# Cyusb3314_Indicator.net
KiCad netlist of a schematic drawn in Altium Designer
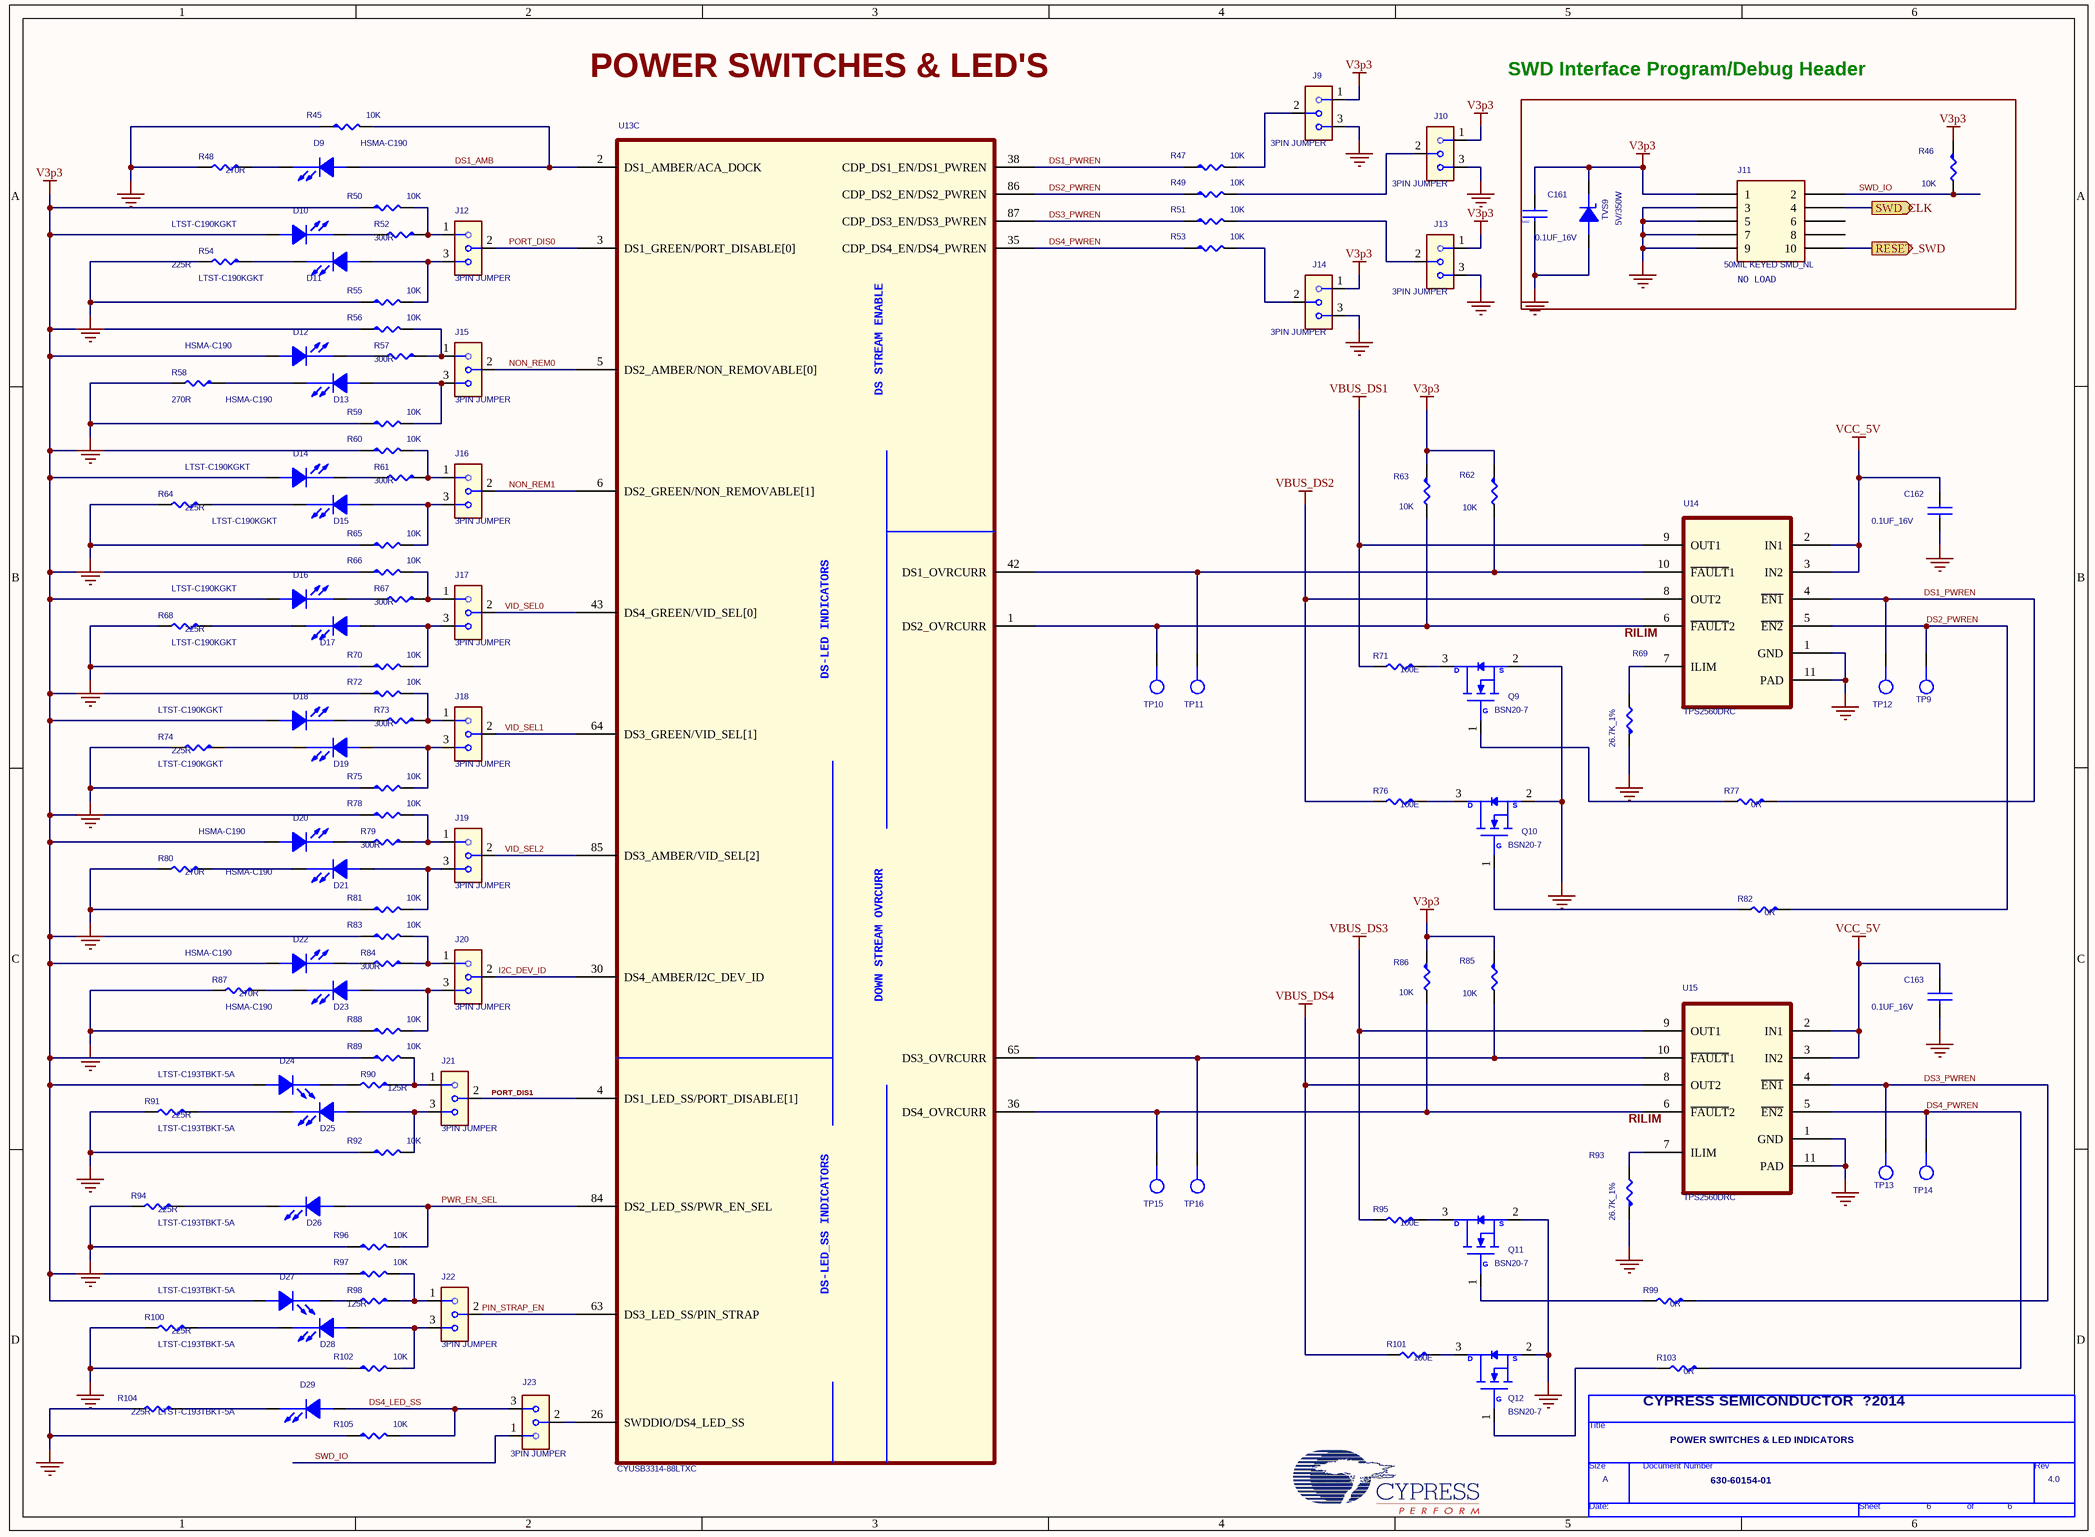
[diagram p0: Cyusb3314_Indicator.SchDoc]

(export (version "E")
  (design (tool "Eeschema 10.0.6"))
  (components
    (comp (ref "C161")
      (value "0.1UF_16V")
      (footprint "CAPC1005X55M")
      (description "CAP .1UF 16V CERAMIC Y5V 0402")
      (fields
        (field (name "CY_PART#") "730R-10010")
        (field (name "MANUFACTURER") "Panasonic - ECG")
        (field (name "CREATED BY") "SNF")
      )
      (libsource (lib "*") (part "0.1 uFd 0402"))
    )
    (comp (ref "C162")
      (value "0.1UF_16V")
      (footprint "CAPC1005X56M")
      (libsource (lib "*") (part "CAPACITOR NON-POL"))
    )
    (comp (ref "C163")
      (value "0.1UF_16V")
      (footprint "CAPC1005X56M")
      (libsource (lib "*") (part "CAPACITOR NON-POL"))
    )
    (comp (ref "D9") (value "HSMA-C190") (libsource (lib "*") (part "LED")))
    (comp (ref "D10") (value "LTST-C190KGKT") (libsource (lib "*") (part "LED")))
    (comp (ref "D11") (value "LTST-C190KGKT") (libsource (lib "*") (part "LED")))
    (comp (ref "D12") (value "HSMA-C190") (libsource (lib "*") (part "LED")))
    (comp (ref "D13") (value "HSMA-C190") (libsource (lib "*") (part "LED")))
    (comp (ref "D14") (value "LTST-C190KGKT") (libsource (lib "*") (part "LED")))
    (comp (ref "D15") (value "LTST-C190KGKT") (libsource (lib "*") (part "LED")))
    (comp (ref "D16") (value "LTST-C190KGKT") (libsource (lib "*") (part "LED")))
    (comp (ref "D17") (value "LTST-C190KGKT") (libsource (lib "*") (part "LED")))
    (comp (ref "D18") (value "LTST-C190KGKT") (libsource (lib "*") (part "LED")))
    (comp (ref "D19") (value "LTST-C190KGKT") (libsource (lib "*") (part "LED")))
    (comp (ref "D20") (value "HSMA-C190") (libsource (lib "*") (part "LED")))
    (comp (ref "D21") (value "HSMA-C190") (libsource (lib "*") (part "LED")))
    (comp (ref "D22") (value "HSMA-C190") (libsource (lib "*") (part "LED")))
    (comp (ref "D23") (value "HSMA-C190") (libsource (lib "*") (part "LED")))
    (comp (ref "D24") (value "LTST-C193TBKT-5A") (libsource (lib "*") (part "LED")))
    (comp (ref "D25") (value "LTST-C193TBKT-5A") (libsource (lib "*") (part "LED")))
    (comp (ref "D26") (value "LTST-C193TBKT-5A") (libsource (lib "*") (part "LED")))
    (comp (ref "D27") (value "LTST-C193TBKT-5A") (libsource (lib "*") (part "LED")))
    (comp (ref "D28") (value "LTST-C193TBKT-5A") (libsource (lib "*") (part "LED")))
    (comp (ref "D29") (value "LTST-C193TBKT-5A") (libsource (lib "*") (part "LED")))
    (comp (ref "J9")
      (value "3PIN JUMPER")
      (description "CONN HEADER VERT 3POS .100 TIN")
      (fields (field (name "PART NUMBER") "3-644456-3") (field (name "MANUFACTURER") "Tyco Electronics"))
      (libsource (lib "") (part "3PIN JUM_1"))
    )
    (comp (ref "J10")
      (value "3PIN JUMPER")
      (description "CONN HEADER VERT 3POS .100 TIN")
      (fields (field (name "MANUFACTURER") "Tyco Electronics") (field (name "PART NUMBER") "3-644456-3"))
      (libsource (lib "") (part "3PIN JUM_1"))
    )
    (comp (ref "J11")
      (value "50MIL KEYED SMD_NL")
      (footprint "SAMTEC_FTSH-105-01-L-DV-K")
      (description "CONN HEADER 10 PIN 50MIL KEYED SMD")
      (fields
        (field (name "PART NUMBER") "FTSH-105-01-L-DV-K")
        (field (name "MANUFACTURER") "Samtec")
        (field (name "LAST EDIT BY") "SNF")
      )
      (libsource (lib "*") (part "10 Pin Header 50mil Keyed SMD"))
    )
    (comp (ref "J12")
      (value "3PIN JUMPER")
      (description "CONN HEADER VERT 3POS .100 TIN")
      (fields (field (name "PART NUMBER") "3-644456-3") (field (name "MANUFACTURER") "Tyco Electronics"))
      (libsource (lib "*") (part "3PIN JUM"))
    )
    (comp (ref "J13")
      (value "3PIN JUMPER")
      (description "CONN HEADER VERT 3POS .100 TIN")
      (fields (field (name "PART NUMBER") "3-644456-3") (field (name "MANUFACTURER") "Tyco Electronics"))
      (libsource (lib "") (part "3PIN JUM_1"))
    )
    (comp (ref "J14")
      (value "3PIN JUMPER")
      (description "CONN HEADER VERT 3POS .100 TIN")
      (fields (field (name "MANUFACTURER") "Tyco Electronics") (field (name "PART NUMBER") "3-644456-3"))
      (libsource (lib "") (part "3PIN JUM_1"))
    )
    (comp (ref "J15")
      (value "3PIN JUMPER")
      (description "CONN HEADER VERT 3POS .100 TIN")
      (fields (field (name "PART NUMBER") "3-644456-3") (field (name "MANUFACTURER") "Tyco Electronics"))
      (libsource (lib "*") (part "3PIN JUM"))
    )
    (comp (ref "J16")
      (value "3PIN JUMPER")
      (description "CONN HEADER VERT 3POS .100 TIN")
      (fields (field (name "PART NUMBER") "3-644456-3") (field (name "MANUFACTURER") "Tyco Electronics"))
      (libsource (lib "*") (part "3PIN JUM"))
    )
    (comp (ref "J17")
      (value "3PIN JUMPER")
      (description "CONN HEADER VERT 3POS .100 TIN")
      (fields (field (name "MANUFACTURER") "Tyco Electronics") (field (name "PART NUMBER") "3-644456-3"))
      (libsource (lib "*") (part "3PIN JUM"))
    )
    (comp (ref "J18")
      (value "3PIN JUMPER")
      (description "CONN HEADER VERT 3POS .100 TIN")
      (fields (field (name "PART NUMBER") "3-644456-3") (field (name "MANUFACTURER") "Tyco Electronics"))
      (libsource (lib "*") (part "3PIN JUM"))
    )
    (comp (ref "J19")
      (value "3PIN JUMPER")
      (description "CONN HEADER VERT 3POS .100 TIN")
      (fields (field (name "MANUFACTURER") "Tyco Electronics") (field (name "PART NUMBER") "3-644456-3"))
      (libsource (lib "*") (part "3PIN JUM"))
    )
    (comp (ref "J20")
      (value "3PIN JUMPER")
      (description "CONN HEADER VERT 3POS .100 TIN")
      (fields (field (name "MANUFACTURER") "Tyco Electronics") (field (name "PART NUMBER") "3-644456-3"))
      (libsource (lib "*") (part "3PIN JUM"))
    )
    (comp (ref "J21")
      (value "3PIN JUMPER")
      (description "CONN HEADER VERT 3POS .100 TIN")
      (fields (field (name "PART NUMBER") "3-644456-3") (field (name "MANUFACTURER") "Tyco Electronics"))
      (libsource (lib "*") (part "3PIN JUM"))
    )
    (comp (ref "J22")
      (value "3PIN JUMPER")
      (description "CONN HEADER VERT 3POS .100 TIN")
      (fields (field (name "PART NUMBER") "3-644456-3") (field (name "MANUFACTURER") "Tyco Electronics"))
      (libsource (lib "*") (part "3PIN JUM"))
    )
    (comp (ref "J23")
      (value "3PIN JUMPER")
      (description "CONN HEADER VERT 3POS .100 TIN")
      (fields (field (name "PART NUMBER") "3-644456-3") (field (name "MANUFACTURER") "Tyco Electronics"))
      (libsource (lib "") (part "3PIN JUM_2"))
    )
    (comp (ref "Q9")
      (value "BSN20-7")
      (description "MOSFET N-CH 50V 500MA SOT23")
      (fields (field (name "MANUFACTURER") "Diodes Inc"))
      (libsource (lib "*") (part "BSN20-7"))
    )
    (comp (ref "Q10")
      (value "BSN20-7")
      (description "MOSFET N-CH 50V 500MA SOT23")
      (fields (field (name "MANUFACTURER") "Diodes Inc"))
      (libsource (lib "*") (part "BSN20-7"))
    )
    (comp (ref "Q11")
      (value "BSN20-7")
      (description "MOSFET N-CH 50V 500MA SOT23")
      (fields (field (name "MANUFACTURER") "Diodes Inc"))
      (libsource (lib "*") (part "BSN20-7"))
    )
    (comp (ref "Q12")
      (value "BSN20-7")
      (description "MOSFET N-CH 50V 500MA SOT23")
      (fields (field (name "MANUFACTURER") "Diodes Inc"))
      (libsource (lib "*") (part "BSN20-7"))
    )
    (comp (ref "R45")
      (value "10K")
      (footprint "RESC1005X40M")
      (description "RES 10.0K OHM 1/10W 1% 0603 SMD")
      (fields (field (name "MANUFACTURER") "Panasonic - ECG") (field (name "PART NUMBER") "ERJ-3EKF1002V"))
      (libsource (lib "*") (part "R_Dup1"))
    )
    (comp (ref "R46")
      (value "10K")
      (footprint "RESC1005X40M")
      (description "RES 10.0K OHM 1/10W 1% 0603 SMD")
      (fields (field (name "MANUFACTURER") "Panasonic - ECG") (field (name "PART NUMBER") "ERJ-3EKF1002V"))
      (libsource (lib "*") (part "R_Dup1"))
    )
    (comp (ref "R47")
      (value "10K")
      (footprint "RESC1005X40M")
      (description "RES 10.0K OHM 1/10W 1% 0603 SMD")
      (fields (field (name "MANUFACTURER") "Panasonic - ECG") (field (name "PART NUMBER") "ERJ-3EKF1002V"))
      (libsource (lib "*") (part "R_Dup1"))
    )
    (comp (ref "R48") (value "270R") (footprint "RESC1608X50M") (libsource (lib "*") (part "R_Dup1")))
    (comp (ref "R49")
      (value "10K")
      (footprint "RESC1005X40M")
      (description "RES 10.0K OHM 1/10W 1% 0603 SMD")
      (fields (field (name "MANUFACTURER") "Panasonic - ECG") (field (name "PART NUMBER") "ERJ-3EKF1002V"))
      (libsource (lib "*") (part "R_Dup1"))
    )
    (comp (ref "R50")
      (value "10K")
      (footprint "RESC1005X40M")
      (description "RES 10.0K OHM 1/10W 1% 0603 SMD")
      (fields (field (name "MANUFACTURER") "Panasonic - ECG") (field (name "PART NUMBER") "ERJ-3EKF1002V"))
      (libsource (lib "*") (part "R_Dup1"))
    )
    (comp (ref "R51")
      (value "10K")
      (footprint "RESC1005X40M")
      (description "RES 10.0K OHM 1/10W 1% 0603 SMD")
      (fields (field (name "MANUFACTURER") "Panasonic - ECG") (field (name "PART NUMBER") "ERJ-3EKF1002V"))
      (libsource (lib "*") (part "R_Dup1"))
    )
    (comp (ref "R52") (value "300R") (footprint "RESC2012X65M") (libsource (lib "*") (part "R_Dup1")))
    (comp (ref "R53")
      (value "10K")
      (footprint "RESC1005X40M")
      (description "RES 10.0K OHM 1/10W 1% 0603 SMD")
      (fields (field (name "MANUFACTURER") "Panasonic - ECG") (field (name "PART NUMBER") "ERJ-3EKF1002V"))
      (libsource (lib "*") (part "R_Dup1"))
    )
    (comp (ref "R54") (value "225R") (footprint "RESC1608X50M") (libsource (lib "*") (part "R_Dup1")))
    (comp (ref "R55")
      (value "10K")
      (footprint "RESC1005X40M")
      (description "RES 10.0K OHM 1/10W 1% 0603 SMD")
      (fields (field (name "MANUFACTURER") "Panasonic - ECG") (field (name "PART NUMBER") "ERJ-3EKF1002V"))
      (libsource (lib "*") (part "R_Dup1"))
    )
    (comp (ref "R56")
      (value "10K")
      (footprint "RESC1005X40M")
      (description "RES 10.0K OHM 1/10W 1% 0603 SMD")
      (fields (field (name "PART NUMBER") "ERJ-3EKF1002V") (field (name "MANUFACTURER") "Panasonic - ECG"))
      (libsource (lib "*") (part "R_Dup1"))
    )
    (comp (ref "R57") (value "300R") (footprint "RESC2012X65M") (libsource (lib "*") (part "R_Dup1")))
    (comp (ref "R58") (value "270R") (footprint "RESC1608X50M") (libsource (lib "*") (part "R_Dup1")))
    (comp (ref "R59")
      (value "10K")
      (footprint "RESC1005X40M")
      (description "RES 10.0K OHM 1/10W 1% 0603 SMD")
      (fields (field (name "PART NUMBER") "ERJ-3EKF1002V") (field (name "MANUFACTURER") "Panasonic - ECG"))
      (libsource (lib "*") (part "R_Dup1"))
    )
    (comp (ref "R60")
      (value "10K")
      (footprint "RESC1005X40M")
      (description "RES 10.0K OHM 1/10W 1% 0603 SMD")
      (fields (field (name "MANUFACTURER") "Panasonic - ECG") (field (name "PART NUMBER") "ERJ-3EKF1002V"))
      (libsource (lib "*") (part "R_Dup1"))
    )
    (comp (ref "R61") (value "300R") (footprint "RESC2012X65M") (libsource (lib "*") (part "R_Dup1")))
    (comp (ref "R62")
      (value "10K")
      (footprint "RESC1005X40M")
      (description "RES 10.0K OHM 1/10W 1% 0603 SMD")
      (fields (field (name "MANUFACTURER") "Panasonic - ECG") (field (name "PART NUMBER") "ERJ-3EKF1002V"))
      (libsource (lib "*") (part "R_Dup1"))
    )
    (comp (ref "R63")
      (value "10K")
      (footprint "RESC1005X40M")
      (description "RES 10.0K OHM 1/10W 1% 0603 SMD")
      (fields (field (name "PART NUMBER") "ERJ-3EKF1002V") (field (name "MANUFACTURER") "Panasonic - ECG"))
      (libsource (lib "*") (part "R_Dup1"))
    )
    (comp (ref "R64") (value "225R") (footprint "RESC1608X50M") (libsource (lib "*") (part "R_Dup1")))
    (comp (ref "R65")
      (value "10K")
      (footprint "RESC1005X40M")
      (description "RES 10.0K OHM 1/10W 1% 0603 SMD")
      (fields (field (name "MANUFACTURER") "Panasonic - ECG") (field (name "PART NUMBER") "ERJ-3EKF1002V"))
      (libsource (lib "*") (part "R_Dup1"))
    )
    (comp (ref "R66")
      (value "10K")
      (footprint "RESC1005X40M")
      (description "RES 10.0K OHM 1/10W 1% 0603 SMD")
      (fields (field (name "PART NUMBER") "ERJ-3EKF1002V") (field (name "MANUFACTURER") "Panasonic - ECG"))
      (libsource (lib "*") (part "R_Dup1"))
    )
    (comp (ref "R67") (value "300R") (footprint "RESC2012X65M") (libsource (lib "*") (part "R_Dup1")))
    (comp (ref "R68") (value "225R") (footprint "RESC1608X50M") (libsource (lib "*") (part "R_Dup1")))
    (comp (ref "R69")
      (value "26.7K_1%")
      (footprint "RESC1005X40M")
      (description "RES 28.0K OHM 1/10W 1% 0402 SMD")
      (fields (field (name "MANUFACTURER") "Panasonic") (field (name "PART NUMBER") "ERJ-2RKF2802X"))
      (libsource (lib "*") (part "R_Dup1"))
    )
    (comp (ref "R70")
      (value "10K")
      (footprint "RESC1005X40M")
      (description "RES 10.0K OHM 1/10W 1% 0603 SMD")
      (fields (field (name "MANUFACTURER") "Panasonic - ECG") (field (name "PART NUMBER") "ERJ-3EKF1002V"))
      (libsource (lib "*") (part "R_Dup1"))
    )
    (comp (ref "R71") (value "100E") (footprint "RESC1608X50M") (libsource (lib "*") (part "R_Dup1")))
    (comp (ref "R72")
      (value "10K")
      (footprint "RESC1005X40M")
      (description "RES 10.0K OHM 1/10W 1% 0603 SMD")
      (fields (field (name "MANUFACTURER") "Panasonic - ECG") (field (name "PART NUMBER") "ERJ-3EKF1002V"))
      (libsource (lib "*") (part "R_Dup1"))
    )
    (comp (ref "R73") (value "300R") (footprint "RESC2012X65M") (libsource (lib "*") (part "R_Dup1")))
    (comp (ref "R74") (value "225R") (footprint "RESC1608X50M") (libsource (lib "*") (part "R_Dup1")))
    (comp (ref "R75")
      (value "10K")
      (footprint "RESC1005X40M")
      (description "RES 10.0K OHM 1/10W 1% 0603 SMD")
      (fields (field (name "MANUFACTURER") "Panasonic - ECG") (field (name "PART NUMBER") "ERJ-3EKF1002V"))
      (libsource (lib "*") (part "R_Dup1"))
    )
    (comp (ref "R76") (value "100E") (footprint "RESC1608X50M") (libsource (lib "*") (part "R_Dup1")))
    (comp (ref "R77") (value "0R") (footprint "RESC1608X50M") (libsource (lib "*") (part "R_Dup1")))
    (comp (ref "R78")
      (value "10K")
      (footprint "RESC1005X40M")
      (description "RES 10.0K OHM 1/10W 1% 0603 SMD")
      (fields (field (name "MANUFACTURER") "Panasonic - ECG") (field (name "PART NUMBER") "ERJ-3EKF1002V"))
      (libsource (lib "*") (part "R_Dup1"))
    )
    (comp (ref "R79") (value "300R") (footprint "RESC2012X65M") (libsource (lib "*") (part "R_Dup1")))
    (comp (ref "R80") (value "270R") (footprint "RESC1608X50M") (libsource (lib "*") (part "R_Dup1")))
    (comp (ref "R81")
      (value "10K")
      (footprint "RESC1005X40M")
      (description "RES 10.0K OHM 1/10W 1% 0603 SMD")
      (fields (field (name "MANUFACTURER") "Panasonic - ECG") (field (name "PART NUMBER") "ERJ-3EKF1002V"))
      (libsource (lib "*") (part "R_Dup1"))
    )
    (comp (ref "R82") (value "0R") (footprint "RESC1608X50M") (libsource (lib "*") (part "R_Dup1")))
    (comp (ref "R83")
      (value "10K")
      (footprint "RESC1005X40M")
      (description "RES 10.0K OHM 1/10W 1% 0603 SMD")
      (fields (field (name "PART NUMBER") "ERJ-3EKF1002V") (field (name "MANUFACTURER") "Panasonic - ECG"))
      (libsource (lib "*") (part "R_Dup1"))
    )
    (comp (ref "R84") (value "300R") (footprint "RESC2012X65M") (libsource (lib "*") (part "R_Dup1")))
    (comp (ref "R85")
      (value "10K")
      (footprint "RESC1005X40M")
      (description "RES 10.0K OHM 1/10W 1% 0603 SMD")
      (fields (field (name "PART NUMBER") "ERJ-3EKF1002V") (field (name "MANUFACTURER") "Panasonic - ECG"))
      (libsource (lib "*") (part "R_Dup1"))
    )
    (comp (ref "R86")
      (value "10K")
      (footprint "RESC1005X40M")
      (description "RES 10.0K OHM 1/10W 1% 0603 SMD")
      (fields (field (name "MANUFACTURER") "Panasonic - ECG") (field (name "PART NUMBER") "ERJ-3EKF1002V"))
      (libsource (lib "*") (part "R_Dup1"))
    )
    (comp (ref "R87") (value "270R") (footprint "RESC1608X50M") (libsource (lib "*") (part "R_Dup1")))
    (comp (ref "R88")
      (value "10K")
      (footprint "RESC1005X40M")
      (description "RES 10.0K OHM 1/10W 1% 0603 SMD")
      (fields (field (name "MANUFACTURER") "Panasonic - ECG") (field (name "PART NUMBER") "ERJ-3EKF1002V"))
      (libsource (lib "*") (part "R_Dup1"))
    )
    (comp (ref "R89")
      (value "10K")
      (footprint "RESC1005X40M")
      (description "RES 10.0K OHM 1/10W 1% 0603 SMD")
      (fields (field (name "MANUFACTURER") "Panasonic - ECG") (field (name "PART NUMBER") "ERJ-3EKF1002V"))
      (libsource (lib "*") (part "R_Dup1"))
    )
    (comp (ref "R90") (value "125R") (footprint "RESC2012X65M") (libsource (lib "*") (part "R_Dup1")))
    (comp (ref "R91") (value "225R") (footprint "RESC1608X50M") (libsource (lib "*") (part "R_Dup1")))
    (comp (ref "R92")
      (value "10K")
      (footprint "RESC1005X40M")
      (description "RES 10.0K OHM 1/10W 1% 0603 SMD")
      (fields (field (name "PART NUMBER") "ERJ-3EKF1002V") (field (name "MANUFACTURER") "Panasonic - ECG"))
      (libsource (lib "*") (part "R_Dup1"))
    )
    (comp (ref "R93")
      (value "26.7K_1%")
      (footprint "RESC1005X40M")
      (description "RES 28.0K OHM 1/10W 1% 0402 SMD")
      (fields (field (name "TOLERANCE") "1%") (field (name "PART NUMBER") "ERJ-2RKF2802X"))
      (libsource (lib "*") (part "R_Dup1"))
    )
    (comp (ref "R94") (value "225R") (footprint "RESC1608X50M") (libsource (lib "*") (part "R_Dup1")))
    (comp (ref "R95") (value "100E") (footprint "RESC1608X50M") (libsource (lib "*") (part "R_Dup1")))
    (comp (ref "R96")
      (value "10K")
      (footprint "RESC1005X40M")
      (description "RES 10.0K OHM 1/10W 1% 0603 SMD")
      (fields (field (name "MANUFACTURER") "Panasonic - ECG") (field (name "PART NUMBER") "ERJ-3EKF1002V"))
      (libsource (lib "*") (part "R_Dup1"))
    )
    (comp (ref "R97")
      (value "10K")
      (footprint "RESC1005X40M")
      (description "RES 10.0K OHM 1/10W 1% 0603 SMD")
      (fields (field (name "MANUFACTURER") "Panasonic - ECG") (field (name "PART NUMBER") "ERJ-3EKF1002V"))
      (libsource (lib "*") (part "R_Dup1"))
    )
    (comp (ref "R98") (value "125R") (footprint "RESC2012X65M") (libsource (lib "*") (part "R_Dup1")))
    (comp (ref "R99") (value "0R") (footprint "RESC1608X50M") (libsource (lib "*") (part "R_Dup1")))
    (comp (ref "R100") (value "225R") (footprint "RESC1608X50M") (libsource (lib "*") (part "R_Dup1")))
    (comp (ref "R101") (value "100E") (footprint "RESC1608X50M") (libsource (lib "*") (part "R_Dup1")))
    (comp (ref "R102")
      (value "10K")
      (footprint "RESC1005X40M")
      (description "RES 10.0K OHM 1/10W 1% 0603 SMD")
      (fields (field (name "MANUFACTURER") "Panasonic - ECG") (field (name "PART NUMBER") "ERJ-3EKF1002V"))
      (libsource (lib "*") (part "R_Dup1"))
    )
    (comp (ref "R103") (value "0R") (footprint "RESC1608X50M") (libsource (lib "*") (part "R_Dup1")))
    (comp (ref "R104") (value "225R") (footprint "RESC1608X50M") (libsource (lib "*") (part "R_Dup1")))
    (comp (ref "R105")
      (value "10K")
      (footprint "RESC1005X40M")
      (description "RES 10.0K OHM 1/10W 1% 0603 SMD")
      (fields (field (name "MANUFACTURER") "Panasonic - ECG") (field (name "PART NUMBER") "ERJ-3EKF1002V"))
      (libsource (lib "*") (part "R_Dup1"))
    )
    (comp (ref "TP9")
      (value "TP_YEL")
      (footprint "KEYSTONE_5000")
      (description "TEST POINT PC MINI .040\"D RED")
      (fields (field (name "MANUFACTURER") "Keystone") (field (name "PART NUMBER") "5000"))
      (libsource (lib "*") (part "TP"))
    )
    (comp (ref "TP10") (value "TEST POINT") (footprint "TP25C50") (libsource (lib "*") (part "TP")))
    (comp (ref "TP11")
      (value "TP_YEL")
      (footprint "KEYSTONE_5000")
      (description "TEST POINT PC MINI .040\"D RED")
      (fields (field (name "PART NUMBER") "5000") (field (name "MANUFACTURER") "Keystone"))
      (libsource (lib "*") (part "TP"))
    )
    (comp (ref "TP12") (value "TEST POINT") (footprint "TP25C50") (libsource (lib "*") (part "TP")))
    (comp (ref "TP13")
      (value "TP_YEL")
      (footprint "KEYSTONE_5000")
      (description "TEST POINT PC MINI .040\"D RED")
      (fields (field (name "MANUFACTURER") "Keystone") (field (name "PART NUMBER") "5000"))
      (libsource (lib "*") (part "TP"))
    )
    (comp (ref "TP14") (value "TEST POINT") (footprint "TP25C50") (libsource (lib "*") (part "TP")))
    (comp (ref "TP15") (value "TEST POINT") (footprint "TP25C50") (libsource (lib "*") (part "TP")))
    (comp (ref "TP16")
      (value "TP_YEL")
      (footprint "KEYSTONE_5000")
      (description "TEST POINT PC MINI .040\"D RED")
      (fields (field (name "PART NUMBER") "5000") (field (name "MANUFACTURER") "Keystone"))
      (libsource (lib "*") (part "TP"))
    )
    (comp (ref "TVS9")
      (value "5V/350W")
      (footprint "SOD2513X120M")
      (description "TVS UNIDIR 350W 5V SOD-323")
      (fields
        (field (name "PART NUMBER") "SD05.TCT")
        (field (name "MANUFACTURER") "Dioded Inc.")
        (field (name "LASTEDITBY") "gir")
      )
      (libsource (lib "*") (part "TVS 5V SOD-323_0"))
    )
    (comp (ref "U13")
      (value "CYUSB3314-88LTXC")
      (footprint "QFN40P1000X1000X100-89M")
      (libsource (lib "*") (part "CYUSB3314-88LTXC_2"))
    )
    (comp (ref "U14")
      (value "TPS2560DRC")
      (footprint "SON50P300X300X100-11M")
      (libsource (lib "*") (part "TPS2560DRC"))
    )
    (comp (ref "U15")
      (value "TPS2560DRC")
      (footprint "SON50P300X300X100-11M")
      (libsource (lib "*") (part "TPS2560DRC"))
    )
  )
  (nets
    (net (code "1") (name "/DS1_AMB") (class "Default")
      (node (ref "D9") (pin "1") (pinfunction "ANODE_1") (pintype "passive"))
      (node (ref "R45") (pin "2") (pinfunction "2_2") (pintype "passive"))
      (node (ref "U13") (pin "2") (pinfunction "DS1_AMBER/ACA_DOCK_2") (pintype "passive"))
    )
    (net (code "2") (name "/DS1_PWREN") (class "Default")
      (node (ref "R47") (pin "1") (pinfunction "1_1") (pintype "passive"))
      (node (ref "R77") (pin "1") (pinfunction "1_1") (pintype "passive"))
      (node (ref "TP12") (pin "1") (pinfunction "TP_1") (pintype "passive"))
      (node (ref "U13") (pin "38") (pinfunction "CDP_DS1_EN/DS1_PWREN_38") (pintype "passive"))
      (node (ref "U14") (pin "4") (pinfunction "~{EN1}_4") (pintype "passive"))
    )
    (net (code "3") (name "/DS2_PWREN") (class "Default")
      (node (ref "R49") (pin "1") (pinfunction "1_1") (pintype "passive"))
      (node (ref "R82") (pin "1") (pinfunction "1_1") (pintype "passive"))
      (node (ref "TP9") (pin "1") (pinfunction "TP_1") (pintype "passive"))
      (node (ref "U13") (pin "86") (pinfunction "CDP_DS2_EN/DS2_PWREN_86") (pintype "passive"))
      (node (ref "U14") (pin "5") (pinfunction "~{EN2}_5") (pintype "passive"))
    )
    (net (code "4") (name "/DS3_PWREN") (class "Default")
      (node (ref "R51") (pin "1") (pinfunction "1_1") (pintype "passive"))
      (node (ref "R99") (pin "1") (pinfunction "1_1") (pintype "passive"))
      (node (ref "TP13") (pin "1") (pinfunction "TP_1") (pintype "passive"))
      (node (ref "U13") (pin "87") (pinfunction "CDP_DS3_EN/DS3_PWREN_87") (pintype "passive"))
      (node (ref "U15") (pin "4") (pinfunction "~{EN1}_4") (pintype "passive"))
    )
    (net (code "5") (name "/DS4_LED_SS") (class "Default")
      (node (ref "D29") (pin "1") (pinfunction "ANODE_1") (pintype "passive"))
      (node (ref "J23") (pin "3") (pinfunction "3_3") (pintype "passive"))
      (node (ref "R105") (pin "2") (pinfunction "2_2") (pintype "passive"))
    )
    (net (code "6") (name "/DS4_PWREN") (class "Default")
      (node (ref "R103") (pin "1") (pinfunction "1_1") (pintype "passive"))
      (node (ref "R53") (pin "1") (pinfunction "1_1") (pintype "passive"))
      (node (ref "TP14") (pin "1") (pinfunction "TP_1") (pintype "passive"))
      (node (ref "U13") (pin "35") (pinfunction "CDP_DS4_EN/DS4_PWREN_35") (pintype "passive"))
      (node (ref "U15") (pin "5") (pinfunction "~{EN2}_5") (pintype "passive"))
    )
    (net (code "7") (name "/I2C_DEV_ID") (class "Default")
      (node (ref "J20") (pin "2") (pinfunction "2_2") (pintype "passive"))
      (node (ref "U13") (pin "30") (pinfunction "DS4_AMBER/I2C_DEV_ID_30") (pintype "passive"))
    )
    (net (code "8") (name "/NON_REM0") (class "Default")
      (node (ref "J15") (pin "2") (pinfunction "2_2") (pintype "passive"))
      (node (ref "U13") (pin "5") (pinfunction "DS2_AMBER/NON_REMOVABLE[0]_5") (pintype "passive"))
    )
    (net (code "9") (name "/NON_REM1") (class "Default")
      (node (ref "J16") (pin "2") (pinfunction "2_2") (pintype "passive"))
      (node (ref "U13") (pin "6") (pinfunction "DS2_GREEN/NON_REMOVABLE[1]_6") (pintype "passive"))
    )
    (net (code "10") (name "/PIN_STRAP_EN") (class "Default")
      (node (ref "J22") (pin "2") (pinfunction "2_2") (pintype "passive"))
      (node (ref "U13") (pin "63") (pinfunction "DS3_LED_SS/PIN_STRAP_63") (pintype "passive"))
    )
    (net (code "11") (name "/PORT_DIS0") (class "Default")
      (node (ref "J12") (pin "2") (pinfunction "2_2") (pintype "passive"))
      (node (ref "U13") (pin "3") (pinfunction "DS1_GREEN/PORT_DISABLE[0]_3") (pintype "passive"))
    )
    (net (code "12") (name "/PORT_DIS1") (class "Default")
      (node (ref "J21") (pin "2") (pinfunction "2_2") (pintype "passive"))
      (node (ref "U13") (pin "4") (pinfunction "DS1_LED_SS/PORT_DISABLE[1]_4") (pintype "passive"))
    )
    (net (code "13") (name "/PWR_EN_SEL") (class "Default")
      (node (ref "D26") (pin "1") (pinfunction "ANODE_1") (pintype "passive"))
      (node (ref "R96") (pin "2") (pinfunction "2_2") (pintype "passive"))
      (node (ref "U13") (pin "84") (pinfunction "DS2_LED_SS/PWR_EN_SEL_84") (pintype "passive"))
    )
    (net (code "14") (name "/RESET_SWD") (class "Default")
      (node (ref "J11") (pin "10") (pinfunction "10_10") (pintype "passive"))
    )
    (net (code "15") (name "/SWD_CLK") (class "Default")
      (node (ref "J11") (pin "4") (pinfunction "4_4") (pintype "passive"))
    )
    (net (code "16") (name "/SWD_IO") (class "Default")
      (node (ref "J11") (pin "2") (pinfunction "2_2") (pintype "passive"))
      (node (ref "J23") (pin "1") (pinfunction "1_1") (pintype "passive"))
      (node (ref "R46") (pin "2") (pinfunction "2_2") (pintype "passive"))
    )
    (net (code "17") (name "/VID_SEL0") (class "Default")
      (node (ref "J17") (pin "2") (pinfunction "2_2") (pintype "passive"))
      (node (ref "U13") (pin "43") (pinfunction "DS4_GREEN/VID_SEL[0]_43") (pintype "passive"))
    )
    (net (code "18") (name "/VID_SEL1") (class "Default")
      (node (ref "J18") (pin "2") (pinfunction "2_2") (pintype "passive"))
      (node (ref "U13") (pin "64") (pinfunction "DS3_GREEN/VID_SEL[1]_64") (pintype "passive"))
    )
    (net (code "19") (name "/VID_SEL2") (class "Default")
      (node (ref "J19") (pin "2") (pinfunction "2_2") (pintype "passive"))
      (node (ref "U13") (pin "85") (pinfunction "DS3_AMBER/VID_SEL[2]_85") (pintype "passive"))
    )
    (net (code "20") (name "GND") (class "Default")
      (node (ref "C161") (pin "2") (pinfunction "2_2") (pintype "passive"))
      (node (ref "C162") (pin "2") (pinfunction "2_2") (pintype "passive"))
      (node (ref "C163") (pin "2") (pinfunction "2_2") (pintype "passive"))
      (node (ref "J10") (pin "3") (pinfunction "3_3") (pintype "passive"))
      (node (ref "J11") (pin "3") (pinfunction "3_3") (pintype "passive"))
      (node (ref "J11") (pin "5") (pinfunction "5_5") (pintype "passive"))
      (node (ref "J11") (pin "7") (pinfunction "7_7") (pintype "passive"))
      (node (ref "J11") (pin "9") (pinfunction "9_9") (pintype "passive"))
      (node (ref "J13") (pin "3") (pinfunction "3_3") (pintype "passive"))
      (node (ref "J14") (pin "3") (pinfunction "3_3") (pintype "passive"))
      (node (ref "J9") (pin "3") (pinfunction "3_3") (pintype "passive"))
      (node (ref "Q10") (pin "2") (pinfunction "S_2") (pintype "passive"))
      (node (ref "Q11") (pin "2") (pinfunction "S_2") (pintype "passive"))
      (node (ref "Q12") (pin "2") (pinfunction "S_2") (pintype "passive"))
      (node (ref "Q9") (pin "2") (pinfunction "S_2") (pintype "passive"))
      (node (ref "R100") (pin "2") (pinfunction "2_2") (pintype "passive"))
      (node (ref "R102") (pin "1") (pinfunction "1_1") (pintype "passive"))
      (node (ref "R104") (pin "2") (pinfunction "2_2") (pintype "passive"))
      (node (ref "R105") (pin "1") (pinfunction "1_1") (pintype "passive"))
      (node (ref "R45") (pin "1") (pinfunction "1_1") (pintype "passive"))
      (node (ref "R48") (pin "2") (pinfunction "2_2") (pintype "passive"))
      (node (ref "R54") (pin "2") (pinfunction "2_2") (pintype "passive"))
      (node (ref "R55") (pin "1") (pinfunction "1_1") (pintype "passive"))
      (node (ref "R58") (pin "2") (pinfunction "2_2") (pintype "passive"))
      (node (ref "R59") (pin "1") (pinfunction "1_1") (pintype "passive"))
      (node (ref "R64") (pin "2") (pinfunction "2_2") (pintype "passive"))
      (node (ref "R65") (pin "1") (pinfunction "1_1") (pintype "passive"))
      (node (ref "R68") (pin "2") (pinfunction "2_2") (pintype "passive"))
      (node (ref "R69") (pin "1") (pinfunction "1_1") (pintype "passive"))
      (node (ref "R70") (pin "1") (pinfunction "1_1") (pintype "passive"))
      (node (ref "R74") (pin "2") (pinfunction "2_2") (pintype "passive"))
      (node (ref "R75") (pin "1") (pinfunction "1_1") (pintype "passive"))
      (node (ref "R80") (pin "2") (pinfunction "2_2") (pintype "passive"))
      (node (ref "R81") (pin "1") (pinfunction "1_1") (pintype "passive"))
      (node (ref "R87") (pin "2") (pinfunction "2_2") (pintype "passive"))
      (node (ref "R88") (pin "1") (pinfunction "1_1") (pintype "passive"))
      (node (ref "R91") (pin "2") (pinfunction "2_2") (pintype "passive"))
      (node (ref "R92") (pin "1") (pinfunction "1_1") (pintype "passive"))
      (node (ref "R93") (pin "1") (pinfunction "1_1") (pintype "passive"))
      (node (ref "R94") (pin "2") (pinfunction "2_2") (pintype "passive"))
      (node (ref "R96") (pin "1") (pinfunction "1_1") (pintype "passive"))
      (node (ref "TVS9") (pin "2") (pinfunction "A_2") (pintype "passive"))
      (node (ref "U14") (pin "1") (pinfunction "GND_1") (pintype "passive"))
      (node (ref "U14") (pin "11") (pinfunction "PAD_11") (pintype "passive"))
      (node (ref "U15") (pin "1") (pinfunction "GND_1") (pintype "passive"))
      (node (ref "U15") (pin "11") (pinfunction "PAD_11") (pintype "passive"))
    )
    (net (code "21") (name "Net-(D9-CATHODE)") (class "Default")
      (node (ref "D9") (pin "2") (pinfunction "CATHODE_2") (pintype "passive"))
      (node (ref "R48") (pin "1") (pinfunction "1_1") (pintype "passive"))
    )
    (net (code "22") (name "Net-(D10-CATHODE)") (class "Default")
      (node (ref "D10") (pin "2") (pinfunction "CATHODE_2") (pintype "passive"))
      (node (ref "R52") (pin "2") (pinfunction "2_2") (pintype "passive"))
    )
    (net (code "23") (name "Net-(D11-ANODE)") (class "Default")
      (node (ref "D11") (pin "1") (pinfunction "ANODE_1") (pintype "passive"))
      (node (ref "J12") (pin "3") (pinfunction "3_3") (pintype "passive"))
      (node (ref "R55") (pin "2") (pinfunction "2_2") (pintype "passive"))
    )
    (net (code "24") (name "Net-(D11-CATHODE)") (class "Default")
      (node (ref "D11") (pin "2") (pinfunction "CATHODE_2") (pintype "passive"))
      (node (ref "R54") (pin "1") (pinfunction "1_1") (pintype "passive"))
    )
    (net (code "25") (name "Net-(D12-CATHODE)") (class "Default")
      (node (ref "D12") (pin "2") (pinfunction "CATHODE_2") (pintype "passive"))
      (node (ref "R57") (pin "2") (pinfunction "2_2") (pintype "passive"))
    )
    (net (code "26") (name "Net-(D13-ANODE)") (class "Default")
      (node (ref "D13") (pin "1") (pinfunction "ANODE_1") (pintype "passive"))
      (node (ref "J15") (pin "3") (pinfunction "3_3") (pintype "passive"))
      (node (ref "R59") (pin "2") (pinfunction "2_2") (pintype "passive"))
    )
    (net (code "27") (name "Net-(D13-CATHODE)") (class "Default")
      (node (ref "D13") (pin "2") (pinfunction "CATHODE_2") (pintype "passive"))
      (node (ref "R58") (pin "1") (pinfunction "1_1") (pintype "passive"))
    )
    (net (code "28") (name "Net-(D14-CATHODE)") (class "Default")
      (node (ref "D14") (pin "2") (pinfunction "CATHODE_2") (pintype "passive"))
      (node (ref "R61") (pin "2") (pinfunction "2_2") (pintype "passive"))
    )
    (net (code "29") (name "Net-(D15-ANODE)") (class "Default")
      (node (ref "D15") (pin "1") (pinfunction "ANODE_1") (pintype "passive"))
      (node (ref "J16") (pin "3") (pinfunction "3_3") (pintype "passive"))
      (node (ref "R65") (pin "2") (pinfunction "2_2") (pintype "passive"))
    )
    (net (code "30") (name "Net-(D15-CATHODE)") (class "Default")
      (node (ref "D15") (pin "2") (pinfunction "CATHODE_2") (pintype "passive"))
      (node (ref "R64") (pin "1") (pinfunction "1_1") (pintype "passive"))
    )
    (net (code "31") (name "Net-(D16-CATHODE)") (class "Default")
      (node (ref "D16") (pin "2") (pinfunction "CATHODE_2") (pintype "passive"))
      (node (ref "R67") (pin "2") (pinfunction "2_2") (pintype "passive"))
    )
    (net (code "32") (name "Net-(D17-ANODE)") (class "Default")
      (node (ref "D17") (pin "1") (pinfunction "ANODE_1") (pintype "passive"))
      (node (ref "J17") (pin "3") (pinfunction "3_3") (pintype "passive"))
      (node (ref "R70") (pin "2") (pinfunction "2_2") (pintype "passive"))
    )
    (net (code "33") (name "Net-(D17-CATHODE)") (class "Default")
      (node (ref "D17") (pin "2") (pinfunction "CATHODE_2") (pintype "passive"))
      (node (ref "R68") (pin "1") (pinfunction "1_1") (pintype "passive"))
    )
    (net (code "34") (name "Net-(D18-CATHODE)") (class "Default")
      (node (ref "D18") (pin "2") (pinfunction "CATHODE_2") (pintype "passive"))
      (node (ref "R73") (pin "2") (pinfunction "2_2") (pintype "passive"))
    )
    (net (code "35") (name "Net-(D19-ANODE)") (class "Default")
      (node (ref "D19") (pin "1") (pinfunction "ANODE_1") (pintype "passive"))
      (node (ref "J18") (pin "3") (pinfunction "3_3") (pintype "passive"))
      (node (ref "R75") (pin "2") (pinfunction "2_2") (pintype "passive"))
    )
    (net (code "36") (name "Net-(D19-CATHODE)") (class "Default")
      (node (ref "D19") (pin "2") (pinfunction "CATHODE_2") (pintype "passive"))
      (node (ref "R74") (pin "1") (pinfunction "1_1") (pintype "passive"))
    )
    (net (code "37") (name "Net-(D20-CATHODE)") (class "Default")
      (node (ref "D20") (pin "2") (pinfunction "CATHODE_2") (pintype "passive"))
      (node (ref "R79") (pin "2") (pinfunction "2_2") (pintype "passive"))
    )
    (net (code "38") (name "Net-(D21-ANODE)") (class "Default")
      (node (ref "D21") (pin "1") (pinfunction "ANODE_1") (pintype "passive"))
      (node (ref "J19") (pin "3") (pinfunction "3_3") (pintype "passive"))
      (node (ref "R81") (pin "2") (pinfunction "2_2") (pintype "passive"))
    )
    (net (code "39") (name "Net-(D21-CATHODE)") (class "Default")
      (node (ref "D21") (pin "2") (pinfunction "CATHODE_2") (pintype "passive"))
      (node (ref "R80") (pin "1") (pinfunction "1_1") (pintype "passive"))
    )
    (net (code "40") (name "Net-(D22-CATHODE)") (class "Default")
      (node (ref "D22") (pin "2") (pinfunction "CATHODE_2") (pintype "passive"))
      (node (ref "R84") (pin "2") (pinfunction "2_2") (pintype "passive"))
    )
    (net (code "41") (name "Net-(D23-ANODE)") (class "Default")
      (node (ref "D23") (pin "1") (pinfunction "ANODE_1") (pintype "passive"))
      (node (ref "J20") (pin "3") (pinfunction "3_3") (pintype "passive"))
      (node (ref "R88") (pin "2") (pinfunction "2_2") (pintype "passive"))
    )
    (net (code "42") (name "Net-(D23-CATHODE)") (class "Default")
      (node (ref "D23") (pin "2") (pinfunction "CATHODE_2") (pintype "passive"))
      (node (ref "R87") (pin "1") (pinfunction "1_1") (pintype "passive"))
    )
    (net (code "43") (name "Net-(D24-CATHODE)") (class "Default")
      (node (ref "D24") (pin "2") (pinfunction "CATHODE_2") (pintype "passive"))
      (node (ref "R90") (pin "2") (pinfunction "2_2") (pintype "passive"))
    )
    (net (code "44") (name "Net-(D25-ANODE)") (class "Default")
      (node (ref "D25") (pin "1") (pinfunction "ANODE_1") (pintype "passive"))
      (node (ref "J21") (pin "3") (pinfunction "3_3") (pintype "passive"))
      (node (ref "R92") (pin "2") (pinfunction "2_2") (pintype "passive"))
    )
    (net (code "45") (name "Net-(D25-CATHODE)") (class "Default")
      (node (ref "D25") (pin "2") (pinfunction "CATHODE_2") (pintype "passive"))
      (node (ref "R91") (pin "1") (pinfunction "1_1") (pintype "passive"))
    )
    (net (code "46") (name "Net-(D26-CATHODE)") (class "Default")
      (node (ref "D26") (pin "2") (pinfunction "CATHODE_2") (pintype "passive"))
      (node (ref "R94") (pin "1") (pinfunction "1_1") (pintype "passive"))
    )
    (net (code "47") (name "Net-(D27-CATHODE)") (class "Default")
      (node (ref "D27") (pin "2") (pinfunction "CATHODE_2") (pintype "passive"))
      (node (ref "R98") (pin "2") (pinfunction "2_2") (pintype "passive"))
    )
    (net (code "48") (name "Net-(D28-ANODE)") (class "Default")
      (node (ref "D28") (pin "1") (pinfunction "ANODE_1") (pintype "passive"))
      (node (ref "J22") (pin "3") (pinfunction "3_3") (pintype "passive"))
      (node (ref "R102") (pin "2") (pinfunction "2_2") (pintype "passive"))
    )
    (net (code "49") (name "Net-(D28-CATHODE)") (class "Default")
      (node (ref "D28") (pin "2") (pinfunction "CATHODE_2") (pintype "passive"))
      (node (ref "R100") (pin "1") (pinfunction "1_1") (pintype "passive"))
    )
    (net (code "50") (name "Net-(D29-CATHODE)") (class "Default")
      (node (ref "D29") (pin "2") (pinfunction "CATHODE_2") (pintype "passive"))
      (node (ref "R104") (pin "1") (pinfunction "1_1") (pintype "passive"))
    )
    (net (code "51") (name "Net-(J9-Pad2)") (class "Default")
      (node (ref "J9") (pin "2") (pinfunction "2_2") (pintype "passive"))
      (node (ref "R47") (pin "2") (pinfunction "2_2") (pintype "passive"))
    )
    (net (code "52") (name "Net-(J10-Pad2)") (class "Default")
      (node (ref "J10") (pin "2") (pinfunction "2_2") (pintype "passive"))
      (node (ref "R49") (pin "2") (pinfunction "2_2") (pintype "passive"))
    )
    (net (code "53") (name "Net-(J12-Pad1)") (class "Default")
      (node (ref "J12") (pin "1") (pinfunction "1_1") (pintype "passive"))
      (node (ref "R50") (pin "2") (pinfunction "2_2") (pintype "passive"))
      (node (ref "R52") (pin "1") (pinfunction "1_1") (pintype "passive"))
    )
    (net (code "54") (name "Net-(J13-Pad2)") (class "Default")
      (node (ref "J13") (pin "2") (pinfunction "2_2") (pintype "passive"))
      (node (ref "R51") (pin "2") (pinfunction "2_2") (pintype "passive"))
    )
    (net (code "55") (name "Net-(J14-Pad2)") (class "Default")
      (node (ref "J14") (pin "2") (pinfunction "2_2") (pintype "passive"))
      (node (ref "R53") (pin "2") (pinfunction "2_2") (pintype "passive"))
    )
    (net (code "56") (name "Net-(J15-Pad1)") (class "Default")
      (node (ref "J15") (pin "1") (pinfunction "1_1") (pintype "passive"))
      (node (ref "R56") (pin "2") (pinfunction "2_2") (pintype "passive"))
      (node (ref "R57") (pin "1") (pinfunction "1_1") (pintype "passive"))
    )
    (net (code "57") (name "Net-(J16-Pad1)") (class "Default")
      (node (ref "J16") (pin "1") (pinfunction "1_1") (pintype "passive"))
      (node (ref "R60") (pin "2") (pinfunction "2_2") (pintype "passive"))
      (node (ref "R61") (pin "1") (pinfunction "1_1") (pintype "passive"))
    )
    (net (code "58") (name "Net-(J17-Pad1)") (class "Default")
      (node (ref "J17") (pin "1") (pinfunction "1_1") (pintype "passive"))
      (node (ref "R66") (pin "2") (pinfunction "2_2") (pintype "passive"))
      (node (ref "R67") (pin "1") (pinfunction "1_1") (pintype "passive"))
    )
    (net (code "59") (name "Net-(J18-Pad1)") (class "Default")
      (node (ref "J18") (pin "1") (pinfunction "1_1") (pintype "passive"))
      (node (ref "R72") (pin "2") (pinfunction "2_2") (pintype "passive"))
      (node (ref "R73") (pin "1") (pinfunction "1_1") (pintype "passive"))
    )
    (net (code "60") (name "Net-(J19-Pad1)") (class "Default")
      (node (ref "J19") (pin "1") (pinfunction "1_1") (pintype "passive"))
      (node (ref "R78") (pin "2") (pinfunction "2_2") (pintype "passive"))
      (node (ref "R79") (pin "1") (pinfunction "1_1") (pintype "passive"))
    )
    (net (code "61") (name "Net-(J20-Pad1)") (class "Default")
      (node (ref "J20") (pin "1") (pinfunction "1_1") (pintype "passive"))
      (node (ref "R83") (pin "2") (pinfunction "2_2") (pintype "passive"))
      (node (ref "R84") (pin "1") (pinfunction "1_1") (pintype "passive"))
    )
    (net (code "62") (name "Net-(J21-Pad1)") (class "Default")
      (node (ref "J21") (pin "1") (pinfunction "1_1") (pintype "passive"))
      (node (ref "R89") (pin "2") (pinfunction "2_2") (pintype "passive"))
      (node (ref "R90") (pin "1") (pinfunction "1_1") (pintype "passive"))
    )
    (net (code "63") (name "Net-(J22-Pad1)") (class "Default")
      (node (ref "J22") (pin "1") (pinfunction "1_1") (pintype "passive"))
      (node (ref "R97") (pin "2") (pinfunction "2_2") (pintype "passive"))
      (node (ref "R98") (pin "1") (pinfunction "1_1") (pintype "passive"))
    )
    (net (code "64") (name "Net-(Q9-D)") (class "Default")
      (node (ref "Q9") (pin "3") (pinfunction "D_3") (pintype "passive"))
      (node (ref "R71") (pin "1") (pinfunction "1_1") (pintype "passive"))
    )
    (net (code "65") (name "Net-(Q9-G)") (class "Default")
      (node (ref "Q9") (pin "1") (pinfunction "G_1") (pintype "passive"))
      (node (ref "R77") (pin "2") (pinfunction "2_2") (pintype "passive"))
    )
    (net (code "66") (name "Net-(Q10-D)") (class "Default")
      (node (ref "Q10") (pin "3") (pinfunction "D_3") (pintype "passive"))
      (node (ref "R76") (pin "1") (pinfunction "1_1") (pintype "passive"))
    )
    (net (code "67") (name "Net-(Q10-G)") (class "Default")
      (node (ref "Q10") (pin "1") (pinfunction "G_1") (pintype "passive"))
      (node (ref "R82") (pin "2") (pinfunction "2_2") (pintype "passive"))
    )
    (net (code "68") (name "Net-(Q11-D)") (class "Default")
      (node (ref "Q11") (pin "3") (pinfunction "D_3") (pintype "passive"))
      (node (ref "R95") (pin "1") (pinfunction "1_1") (pintype "passive"))
    )
    (net (code "69") (name "Net-(Q11-G)") (class "Default")
      (node (ref "Q11") (pin "1") (pinfunction "G_1") (pintype "passive"))
      (node (ref "R99") (pin "2") (pinfunction "2_2") (pintype "passive"))
    )
    (net (code "70") (name "Net-(Q12-D)") (class "Default")
      (node (ref "Q12") (pin "3") (pinfunction "D_3") (pintype "passive"))
      (node (ref "R101") (pin "1") (pinfunction "1_1") (pintype "passive"))
    )
    (net (code "71") (name "Net-(Q12-G)") (class "Default")
      (node (ref "Q12") (pin "1") (pinfunction "G_1") (pintype "passive"))
      (node (ref "R103") (pin "2") (pinfunction "2_2") (pintype "passive"))
    )
    (net (code "72") (name "Net-(TP10-TP)") (class "Default")
      (node (ref "R63") (pin "2") (pinfunction "2_2") (pintype "passive"))
      (node (ref "TP10") (pin "1") (pinfunction "TP_1") (pintype "passive"))
      (node (ref "U13") (pin "1") (pinfunction "DS2_OVRCURR_1") (pintype "passive"))
      (node (ref "U14") (pin "6") (pinfunction "~{FAULT}2_6") (pintype "passive"))
    )
    (net (code "73") (name "Net-(TP11-TP)") (class "Default")
      (node (ref "R62") (pin "2") (pinfunction "2_2") (pintype "passive"))
      (node (ref "TP11") (pin "1") (pinfunction "TP_1") (pintype "passive"))
      (node (ref "U13") (pin "42") (pinfunction "DS1_OVRCURR_42") (pintype "passive"))
      (node (ref "U14") (pin "10") (pinfunction "~{FAULT}1_10") (pintype "passive"))
    )
    (net (code "74") (name "Net-(TP15-TP)") (class "Default")
      (node (ref "R86") (pin "2") (pinfunction "2_2") (pintype "passive"))
      (node (ref "TP15") (pin "1") (pinfunction "TP_1") (pintype "passive"))
      (node (ref "U13") (pin "36") (pinfunction "DS4_OVRCURR_36") (pintype "passive"))
      (node (ref "U15") (pin "6") (pinfunction "~{FAULT}2_6") (pintype "passive"))
    )
    (net (code "75") (name "Net-(TP16-TP)") (class "Default")
      (node (ref "R85") (pin "2") (pinfunction "2_2") (pintype "passive"))
      (node (ref "TP16") (pin "1") (pinfunction "TP_1") (pintype "passive"))
      (node (ref "U13") (pin "65") (pinfunction "DS3_OVRCURR_65") (pintype "passive"))
      (node (ref "U15") (pin "10") (pinfunction "~{FAULT}1_10") (pintype "passive"))
    )
    (net (code "76") (name "Net-(U13C-SWDDIO{slash}DS4_LED_SS)") (class "Default")
      (node (ref "J23") (pin "2") (pinfunction "2_2") (pintype "passive"))
      (node (ref "U13") (pin "26") (pinfunction "SWDDIO/DS4_LED_SS_26") (pintype "passive"))
    )
    (net (code "77") (name "Net-(U14-ILIM)") (class "Default")
      (node (ref "R69") (pin "2") (pinfunction "2_2") (pintype "passive"))
      (node (ref "U14") (pin "7") (pinfunction "ILIM_7") (pintype "passive"))
    )
    (net (code "78") (name "Net-(U15-ILIM)") (class "Default")
      (node (ref "R93") (pin "2") (pinfunction "2_2") (pintype "passive"))
      (node (ref "U15") (pin "7") (pinfunction "ILIM_7") (pintype "passive"))
    )
    (net (code "79") (name "V3p3") (class "Default")
      (node (ref "C161") (pin "1") (pinfunction "1_1") (pintype "passive"))
      (node (ref "D10") (pin "1") (pinfunction "ANODE_1") (pintype "passive"))
      (node (ref "D12") (pin "1") (pinfunction "ANODE_1") (pintype "passive"))
      (node (ref "D14") (pin "1") (pinfunction "ANODE_1") (pintype "passive"))
      (node (ref "D16") (pin "1") (pinfunction "ANODE_1") (pintype "passive"))
      (node (ref "D18") (pin "1") (pinfunction "ANODE_1") (pintype "passive"))
      (node (ref "D20") (pin "1") (pinfunction "ANODE_1") (pintype "passive"))
      (node (ref "D22") (pin "1") (pinfunction "ANODE_1") (pintype "passive"))
      (node (ref "D24") (pin "1") (pinfunction "ANODE_1") (pintype "passive"))
      (node (ref "D27") (pin "1") (pinfunction "ANODE_1") (pintype "passive"))
      (node (ref "J10") (pin "1") (pinfunction "1_1") (pintype "passive"))
      (node (ref "J11") (pin "1") (pinfunction "1_1") (pintype "passive"))
      (node (ref "J13") (pin "1") (pinfunction "1_1") (pintype "passive"))
      (node (ref "J14") (pin "1") (pinfunction "1_1") (pintype "passive"))
      (node (ref "J9") (pin "1") (pinfunction "1_1") (pintype "passive"))
      (node (ref "R46") (pin "1") (pinfunction "1_1") (pintype "passive"))
      (node (ref "R50") (pin "1") (pinfunction "1_1") (pintype "passive"))
      (node (ref "R56") (pin "1") (pinfunction "1_1") (pintype "passive"))
      (node (ref "R60") (pin "1") (pinfunction "1_1") (pintype "passive"))
      (node (ref "R62") (pin "1") (pinfunction "1_1") (pintype "passive"))
      (node (ref "R63") (pin "1") (pinfunction "1_1") (pintype "passive"))
      (node (ref "R66") (pin "1") (pinfunction "1_1") (pintype "passive"))
      (node (ref "R72") (pin "1") (pinfunction "1_1") (pintype "passive"))
      (node (ref "R78") (pin "1") (pinfunction "1_1") (pintype "passive"))
      (node (ref "R83") (pin "1") (pinfunction "1_1") (pintype "passive"))
      (node (ref "R85") (pin "1") (pinfunction "1_1") (pintype "passive"))
      (node (ref "R86") (pin "1") (pinfunction "1_1") (pintype "passive"))
      (node (ref "R89") (pin "1") (pinfunction "1_1") (pintype "passive"))
      (node (ref "R97") (pin "1") (pinfunction "1_1") (pintype "passive"))
      (node (ref "TVS9") (pin "1") (pinfunction "K_1") (pintype "passive"))
    )
    (net (code "80") (name "VBUS_DS1") (class "Default")
      (node (ref "R71") (pin "2") (pinfunction "2_2") (pintype "passive"))
      (node (ref "U14") (pin "9") (pinfunction "OUT1_9") (pintype "passive"))
    )
    (net (code "81") (name "VBUS_DS2") (class "Default")
      (node (ref "R76") (pin "2") (pinfunction "2_2") (pintype "passive"))
      (node (ref "U14") (pin "8") (pinfunction "OUT2_8") (pintype "passive"))
    )
    (net (code "82") (name "VBUS_DS3") (class "Default")
      (node (ref "R95") (pin "2") (pinfunction "2_2") (pintype "passive"))
      (node (ref "U15") (pin "9") (pinfunction "OUT1_9") (pintype "passive"))
    )
    (net (code "83") (name "VBUS_DS4") (class "Default")
      (node (ref "R101") (pin "2") (pinfunction "2_2") (pintype "passive"))
      (node (ref "U15") (pin "8") (pinfunction "OUT2_8") (pintype "passive"))
    )
    (net (code "84") (name "VCC_5V") (class "Default")
      (node (ref "C162") (pin "1") (pinfunction "1_1") (pintype "passive"))
      (node (ref "C163") (pin "1") (pinfunction "1_1") (pintype "passive"))
      (node (ref "U14") (pin "2") (pinfunction "IN1_2") (pintype "passive"))
      (node (ref "U14") (pin "3") (pinfunction "IN2_3") (pintype "passive"))
      (node (ref "U15") (pin "2") (pinfunction "IN1_2") (pintype "passive"))
      (node (ref "U15") (pin "3") (pinfunction "IN2_3") (pintype "passive"))
    )
    (net (code "85") (name "unconnected-(J11-Pad6)") (class "Default")
      (node (ref "J11") (pin "6") (pinfunction "6_6") (pintype "passive"))
    )
    (net (code "86") (name "unconnected-(J11-Pad8)") (class "Default")
      (node (ref "J11") (pin "8") (pinfunction "8_8") (pintype "passive"))
    )
  )
)
